# MicroPlayerSCH.net
KiCad netlist of a schematic drawn in Altium Designer
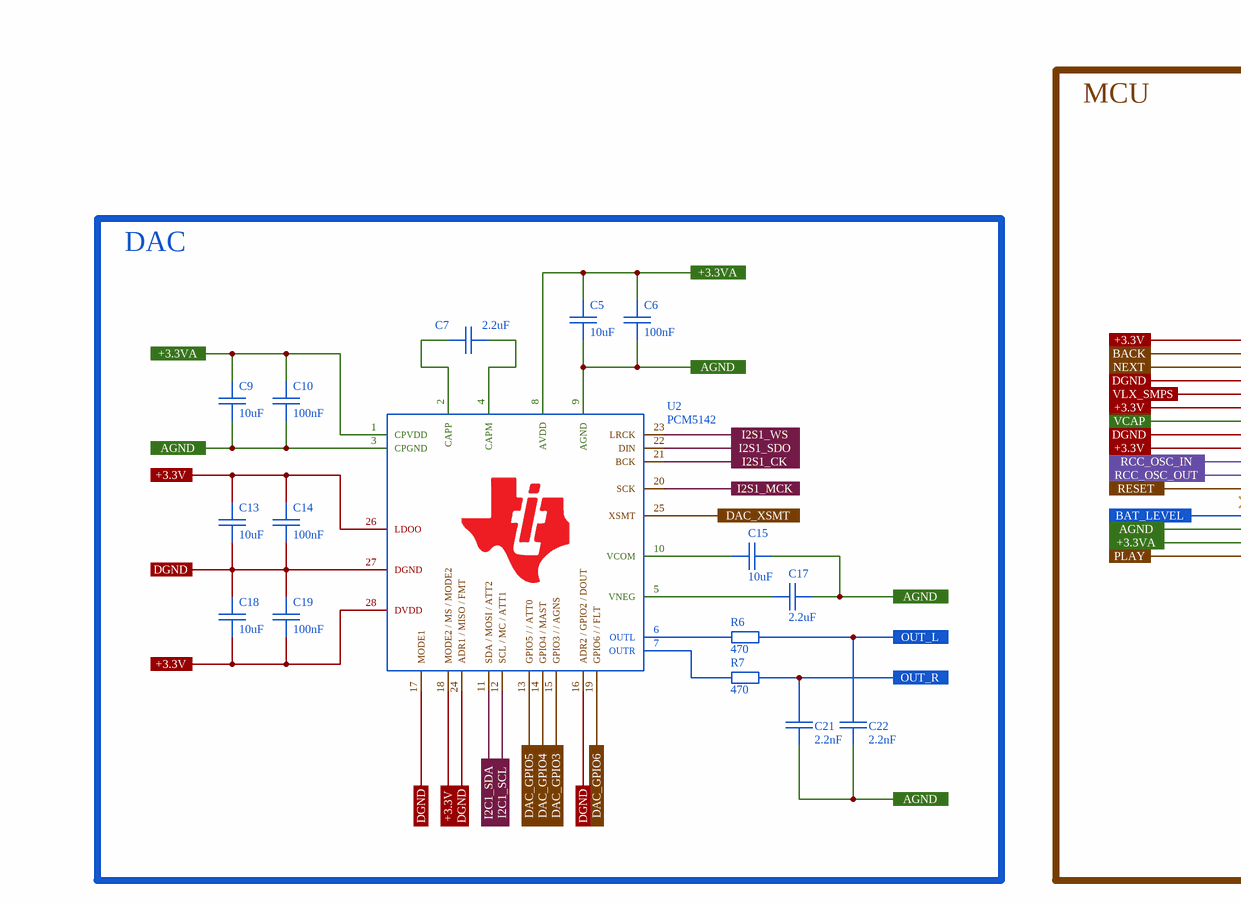
[diagram p0: MicroPlayerSCH.SchDoc, top left]
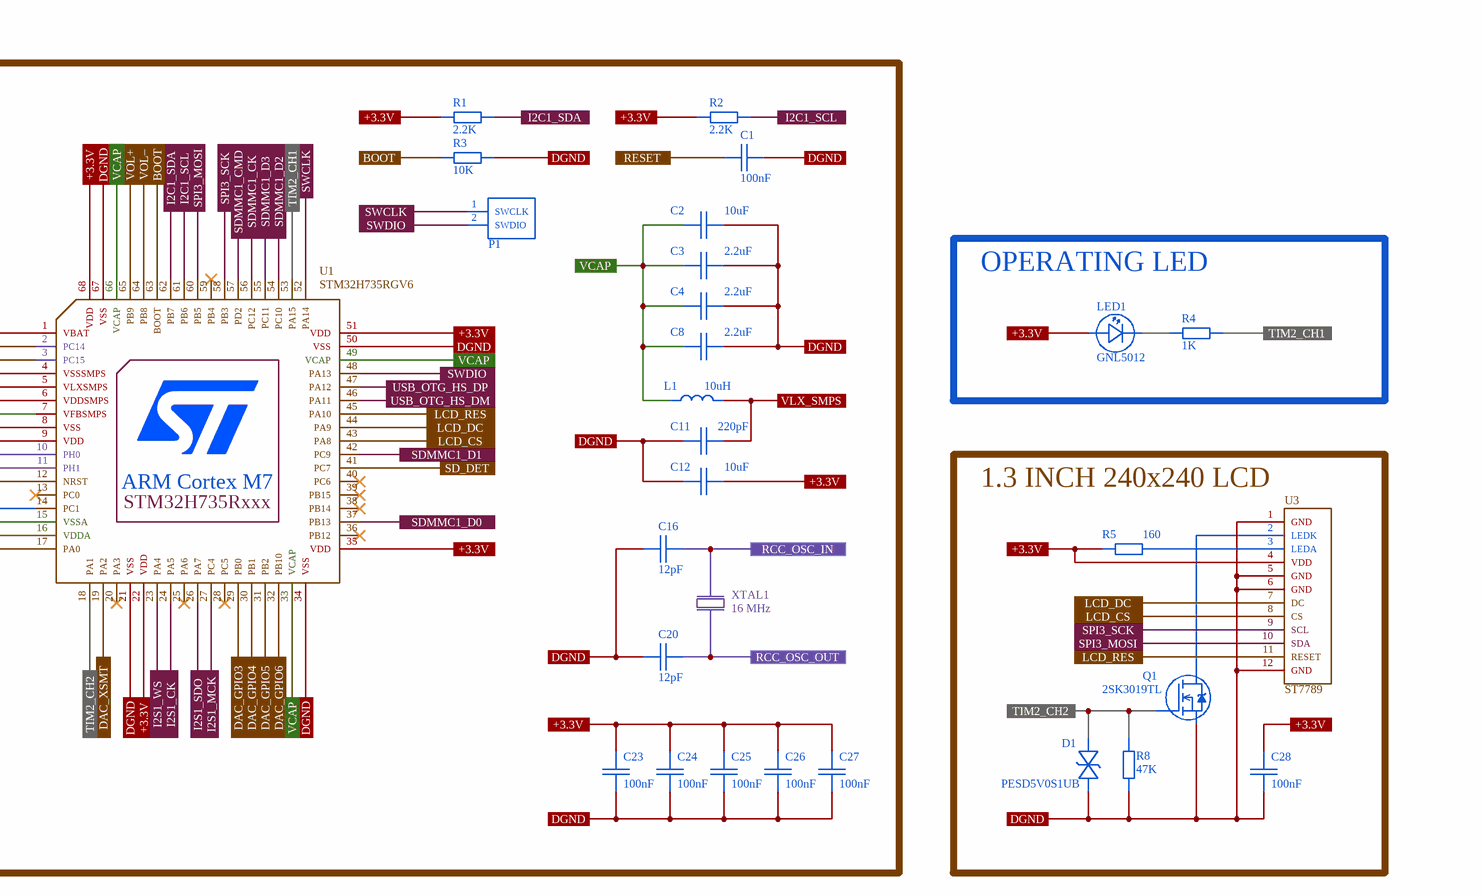
[diagram p1: MicroPlayerSCH.SchDoc, top right]
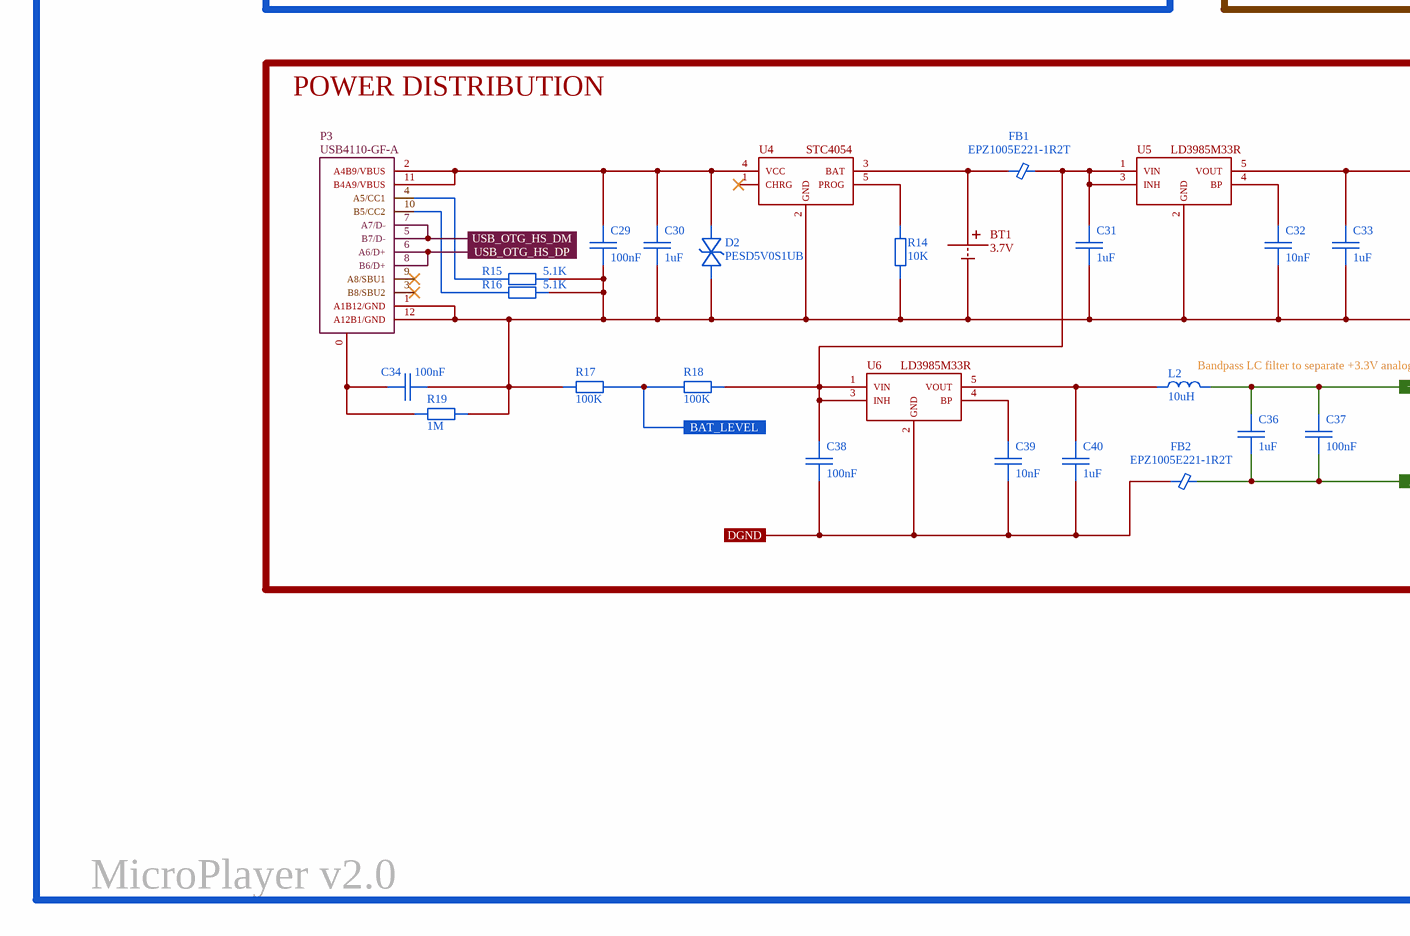
[diagram p2: MicroPlayerSCH.SchDoc, bottom left]
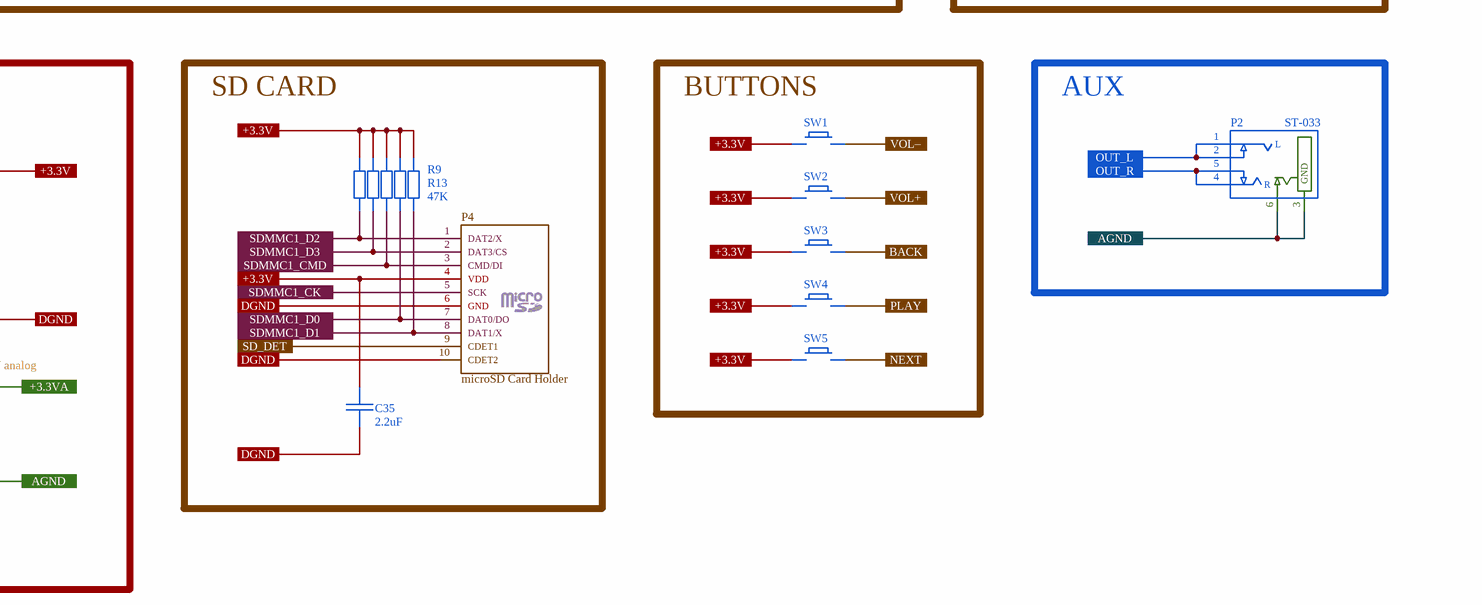
[diagram p3: MicroPlayerSCH.SchDoc, bottom right]

(export (version "E")
  (design (tool "Eeschema 10.0.6"))
  (components
    (comp (ref "BT1") (value "3.7V") (footprint "_2-PAD-SM") (libsource (lib "PowerUnits") (part "Battery")))
    (comp (ref "C1")
      (value "100nF")
      (footprint "C0402")
      (fields (field (name "VOLTAGE") "250V") (field (name "TOLERANCE") "5%"))
      (libsource (lib "CommonElements") (part "Cap"))
    )
    (comp (ref "C2")
      (value "10uF")
      (footprint "C0603")
      (fields (field (name "VOLTAGE") "250V") (field (name "TOLERANCE") "5%"))
      (libsource (lib "CommonElements") (part "Cap"))
    )
    (comp (ref "C3")
      (value "2.2uF")
      (footprint "C0402")
      (fields (field (name "VOLTAGE") "250V") (field (name "TOLERANCE") "5%"))
      (libsource (lib "CommonElements") (part "Cap"))
    )
    (comp (ref "C4")
      (value "2.2uF")
      (footprint "C0402")
      (fields (field (name "VOLTAGE") "250V") (field (name "TOLERANCE") "5%"))
      (libsource (lib "CommonElements") (part "Cap"))
    )
    (comp (ref "C5")
      (value "10uF")
      (footprint "C0603")
      (fields (field (name "VOLTAGE") "250V") (field (name "TOLERANCE") "5%"))
      (libsource (lib "CommonElements") (part "Cap"))
    )
    (comp (ref "C6")
      (value "100nF")
      (footprint "C0402")
      (fields (field (name "VOLTAGE") "250V") (field (name "TOLERANCE") "5%"))
      (libsource (lib "CommonElements") (part "Cap"))
    )
    (comp (ref "C7")
      (value "2.2uF")
      (footprint "C0402")
      (fields (field (name "VOLTAGE") "250V") (field (name "TOLERANCE") "5%"))
      (libsource (lib "CommonElements") (part "Cap"))
    )
    (comp (ref "C8")
      (value "2.2uF")
      (footprint "C0402")
      (fields (field (name "VOLTAGE") "250V") (field (name "TOLERANCE") "5%"))
      (libsource (lib "CommonElements") (part "Cap"))
    )
    (comp (ref "C9")
      (value "10uF")
      (footprint "C0603")
      (fields (field (name "VOLTAGE") "250V") (field (name "TOLERANCE") "5%"))
      (libsource (lib "CommonElements") (part "Cap"))
    )
    (comp (ref "C10")
      (value "100nF")
      (footprint "C0402")
      (fields (field (name "VOLTAGE") "250V") (field (name "TOLERANCE") "5%"))
      (libsource (lib "CommonElements") (part "Cap"))
    )
    (comp (ref "C11")
      (value "220pF")
      (footprint "C0402")
      (fields (field (name "VOLTAGE") "250V") (field (name "TOLERANCE") "5%"))
      (libsource (lib "CommonElements") (part "Cap"))
    )
    (comp (ref "C12")
      (value "10uF")
      (footprint "C0603")
      (fields (field (name "VOLTAGE") "250V") (field (name "TOLERANCE") "5%"))
      (libsource (lib "CommonElements") (part "Cap"))
    )
    (comp (ref "C13")
      (value "10uF")
      (footprint "C0603")
      (fields (field (name "VOLTAGE") "250V") (field (name "TOLERANCE") "5%"))
      (libsource (lib "CommonElements") (part "Cap"))
    )
    (comp (ref "C14")
      (value "100nF")
      (footprint "C0402")
      (fields (field (name "VOLTAGE") "250V") (field (name "TOLERANCE") "5%"))
      (libsource (lib "CommonElements") (part "Cap"))
    )
    (comp (ref "C15")
      (value "10uF")
      (footprint "C0603")
      (fields (field (name "VOLTAGE") "250V") (field (name "TOLERANCE") "5%"))
      (libsource (lib "CommonElements") (part "Cap"))
    )
    (comp (ref "C16")
      (value "12pF")
      (footprint "C0402")
      (fields (field (name "VOLTAGE") "250V") (field (name "TOLERANCE") "5%"))
      (libsource (lib "CommonElements") (part "Cap"))
    )
    (comp (ref "C17")
      (value "2.2uF")
      (footprint "C0402")
      (fields (field (name "VOLTAGE") "250V") (field (name "TOLERANCE") "5%"))
      (libsource (lib "CommonElements") (part "Cap"))
    )
    (comp (ref "C18")
      (value "10uF")
      (footprint "C0603")
      (fields (field (name "VOLTAGE") "250V") (field (name "TOLERANCE") "5%"))
      (libsource (lib "CommonElements") (part "Cap"))
    )
    (comp (ref "C19")
      (value "100nF")
      (footprint "C0402")
      (fields (field (name "VOLTAGE") "250V") (field (name "TOLERANCE") "5%"))
      (libsource (lib "CommonElements") (part "Cap"))
    )
    (comp (ref "C20")
      (value "12pF")
      (footprint "C0402")
      (fields (field (name "VOLTAGE") "250V") (field (name "TOLERANCE") "5%"))
      (libsource (lib "CommonElements") (part "Cap"))
    )
    (comp (ref "C21")
      (value "2.2nF")
      (footprint "C0402")
      (fields (field (name "VOLTAGE") "250V") (field (name "TOLERANCE") "5%"))
      (libsource (lib "CommonElements") (part "Cap"))
    )
    (comp (ref "C22")
      (value "2.2nF")
      (footprint "C0402")
      (fields (field (name "VOLTAGE") "250V") (field (name "TOLERANCE") "5%"))
      (libsource (lib "CommonElements") (part "Cap"))
    )
    (comp (ref "C23")
      (value "100nF")
      (footprint "C0402")
      (fields (field (name "VOLTAGE") "250V") (field (name "TOLERANCE") "5%"))
      (libsource (lib "CommonElements") (part "Cap"))
    )
    (comp (ref "C24")
      (value "100nF")
      (footprint "C0402")
      (fields (field (name "VOLTAGE") "250V") (field (name "TOLERANCE") "5%"))
      (libsource (lib "CommonElements") (part "Cap"))
    )
    (comp (ref "C25")
      (value "100nF")
      (footprint "C0402")
      (fields (field (name "VOLTAGE") "250V") (field (name "TOLERANCE") "5%"))
      (libsource (lib "CommonElements") (part "Cap"))
    )
    (comp (ref "C26")
      (value "100nF")
      (footprint "C0402")
      (fields (field (name "VOLTAGE") "250V") (field (name "TOLERANCE") "5%"))
      (libsource (lib "CommonElements") (part "Cap"))
    )
    (comp (ref "C27")
      (value "100nF")
      (footprint "C0402")
      (fields (field (name "VOLTAGE") "250V") (field (name "TOLERANCE") "5%"))
      (libsource (lib "CommonElements") (part "Cap"))
    )
    (comp (ref "C28")
      (value "100nF")
      (footprint "C0402")
      (fields (field (name "VOLTAGE") "250V") (field (name "TOLERANCE") "5%"))
      (libsource (lib "CommonElements") (part "Cap"))
    )
    (comp (ref "C29")
      (value "100nF")
      (footprint "C0402")
      (fields (field (name "VOLTAGE") "250V") (field (name "TOLERANCE") "5%"))
      (libsource (lib "CommonElements") (part "Cap"))
    )
    (comp (ref "C30")
      (value "1uF")
      (footprint "C0402")
      (fields (field (name "VOLTAGE") "250V") (field (name "TOLERANCE") "5%"))
      (libsource (lib "CommonElements") (part "Cap"))
    )
    (comp (ref "C31")
      (value "1uF")
      (footprint "C0402")
      (fields (field (name "VOLTAGE") "250V") (field (name "TOLERANCE") "5%"))
      (libsource (lib "CommonElements") (part "Cap"))
    )
    (comp (ref "C32")
      (value "10nF")
      (footprint "C0402")
      (fields (field (name "VOLTAGE") "250V") (field (name "TOLERANCE") "5%"))
      (libsource (lib "CommonElements") (part "Cap"))
    )
    (comp (ref "C33")
      (value "1uF")
      (footprint "C0402")
      (fields (field (name "VOLTAGE") "250V") (field (name "TOLERANCE") "5%"))
      (libsource (lib "CommonElements") (part "Cap"))
    )
    (comp (ref "C34")
      (value "100nF")
      (footprint "C0402")
      (fields (field (name "VOLTAGE") "250V") (field (name "TOLERANCE") "5%"))
      (libsource (lib "CommonElements") (part "Cap"))
    )
    (comp (ref "C35")
      (value "2.2uF")
      (footprint "C0402")
      (fields (field (name "VOLTAGE") "250V") (field (name "TOLERANCE") "5%"))
      (libsource (lib "CommonElements") (part "Cap"))
    )
    (comp (ref "C36")
      (value "1uF")
      (footprint "C0402")
      (fields (field (name "VOLTAGE") "250V") (field (name "TOLERANCE") "5%"))
      (libsource (lib "CommonElements") (part "Cap"))
    )
    (comp (ref "C37")
      (value "100nF")
      (footprint "C0402")
      (fields (field (name "VOLTAGE") "250V") (field (name "TOLERANCE") "5%"))
      (libsource (lib "CommonElements") (part "Cap"))
    )
    (comp (ref "C38")
      (value "100nF")
      (footprint "C0402")
      (fields (field (name "VOLTAGE") "250V") (field (name "TOLERANCE") "5%"))
      (libsource (lib "CommonElements") (part "Cap"))
    )
    (comp (ref "C39")
      (value "10nF")
      (footprint "C0402")
      (fields (field (name "VOLTAGE") "250V") (field (name "TOLERANCE") "5%"))
      (libsource (lib "CommonElements") (part "Cap"))
    )
    (comp (ref "C40")
      (value "1uF")
      (footprint "C0402")
      (fields (field (name "VOLTAGE") "250V") (field (name "TOLERANCE") "5%"))
      (libsource (lib "CommonElements") (part "Cap"))
    )
    (comp (ref "D1")
      (value "PESD5V0S1UB")
      (footprint "SOD-523")
      (libsource (lib "CommonElements") (part "Suppressor"))
    )
    (comp (ref "D2")
      (value "PESD5V0S1UB")
      (footprint "SOD-523")
      (libsource (lib "CommonElements") (part "Suppressor"))
    )
    (comp (ref "FB1")
      (value "EPZ1005E221-1R2T")
      (footprint "L0402")
      (libsource (lib "CommonElements") (part "Ferrite Bead"))
    )
    (comp (ref "FB2")
      (value "EPZ1005E221-1R2T")
      (footprint "L0402")
      (libsource (lib "CommonElements") (part "Ferrite Bead"))
    )
    (comp (ref "L1")
      (value "10uH")
      (footprint "L0603")
      (fields (field (name "TOLERANCE") "5%"))
      (libsource (lib "CommonElements") (part "Inductor"))
    )
    (comp (ref "L2")
      (value "10uH")
      (footprint "L0603")
      (fields (field (name "TOLERANCE") "30%") (field (name "PART NUMBER") "LQM21FN100N00K"))
      (libsource (lib "CommonElements") (part "Inductor"))
    )
    (comp (ref "LED1")
      (value "GNL5012")
      (footprint "LED0603")
      (libsource (lib "CommonElements") (part "LED"))
    )
    (comp (ref "P1") (value "P2") (footprint "_2-PAD-SM") (libsource (lib "Connectors") (part "P2")))
    (comp (ref "P2")
      (value "ST-033")
      (footprint "_3-PAD-TH")
      (libsource (lib "Connectors") (part "AJack Socket Stereo"))
    )
    (comp (ref "P3")
      (value "USB4110-GF-A")
      (footprint "USB-TYPE-C")
      (libsource (lib "Connectors") (part "USB Type C with 0"))
    )
    (comp (ref "P4")
      (value "microSD Card Holder")
      (footprint "SD-05")
      (libsource (lib "Connectors") (part "MicroSD-CD2"))
    )
    (comp (ref "Q1")
      (value "2SK3019TL")
      (footprint "SOT-416FL")
      (libsource (lib "CommonElements") (part "MOSFET-N"))
    )
    (comp (ref "R1")
      (value "2.2K")
      (footprint "R0402")
      (fields (field (name "TOLERANCE") "5%") (field (name "POWER") "0.125W"))
      (libsource (lib "CommonElements") (part "Res"))
    )
    (comp (ref "R2")
      (value "2.2K")
      (footprint "R0402")
      (fields (field (name "TOLERANCE") "5%") (field (name "POWER") "0.125W"))
      (libsource (lib "CommonElements") (part "Res"))
    )
    (comp (ref "R3")
      (value "10K")
      (footprint "R0402")
      (fields (field (name "TOLERANCE") "5%") (field (name "POWER") "0.125W"))
      (libsource (lib "CommonElements") (part "Res"))
    )
    (comp (ref "R4")
      (value "1K")
      (footprint "R0402")
      (fields (field (name "TOLERANCE") "5%") (field (name "POWER") "0.125W"))
      (libsource (lib "CommonElements") (part "Res"))
    )
    (comp (ref "R5")
      (value "160")
      (footprint "R0402")
      (fields (field (name "TOLERANCE") "5%") (field (name "POWER") "0.125W"))
      (libsource (lib "CommonElements") (part "Res"))
    )
    (comp (ref "R6")
      (value "470")
      (footprint "R0402")
      (fields (field (name "TOLERANCE") "5%") (field (name "POWER") "0.125W"))
      (libsource (lib "CommonElements") (part "Res"))
    )
    (comp (ref "R7")
      (value "470")
      (footprint "R0402")
      (fields (field (name "TOLERANCE") "5%") (field (name "POWER") "0.125W"))
      (libsource (lib "CommonElements") (part "Res"))
    )
    (comp (ref "R8")
      (value "47K")
      (footprint "R0402")
      (fields (field (name "TOLERANCE") "5%") (field (name "POWER") "0.125W"))
      (libsource (lib "CommonElements") (part "Res"))
    )
    (comp (ref "R9")
      (value "47K")
      (footprint "R0402")
      (fields (field (name "TOLERANCE") "5%") (field (name "POWER") "0.125W"))
      (libsource (lib "CommonElements") (part "Res"))
    )
    (comp (ref "R10")
      (value "47K")
      (footprint "R0402")
      (fields (field (name "TOLERANCE") "5%") (field (name "POWER") "0.125W"))
      (libsource (lib "CommonElements") (part "Res"))
    )
    (comp (ref "R11")
      (value "47K")
      (footprint "R0402")
      (fields (field (name "TOLERANCE") "5%") (field (name "POWER") "0.125W"))
      (libsource (lib "CommonElements") (part "Res"))
    )
    (comp (ref "R12")
      (value "47K")
      (footprint "R0402")
      (fields (field (name "TOLERANCE") "5%") (field (name "POWER") "0.125W"))
      (libsource (lib "CommonElements") (part "Res"))
    )
    (comp (ref "R13")
      (value "47K")
      (footprint "R0402")
      (fields (field (name "TOLERANCE") "5%") (field (name "POWER") "0.125W"))
      (libsource (lib "CommonElements") (part "Res"))
    )
    (comp (ref "R14")
      (value "10K")
      (footprint "R0402")
      (fields (field (name "TOLERANCE") "5%") (field (name "POWER") "0.125W"))
      (libsource (lib "CommonElements") (part "Res"))
    )
    (comp (ref "R15")
      (value "5.1K")
      (footprint "R0402")
      (fields (field (name "TOLERANCE") "5%") (field (name "POWER") "0.125W"))
      (libsource (lib "CommonElements") (part "Res"))
    )
    (comp (ref "R16")
      (value "5.1K")
      (footprint "R0402")
      (fields (field (name "TOLERANCE") "5%") (field (name "POWER") "0.125W"))
      (libsource (lib "CommonElements") (part "Res"))
    )
    (comp (ref "R17")
      (value "100K")
      (footprint "R0402")
      (fields (field (name "TOLERANCE") "5%") (field (name "POWER") "0.125W"))
      (libsource (lib "CommonElements") (part "Res"))
    )
    (comp (ref "R18")
      (value "100K")
      (footprint "R0402")
      (fields (field (name "TOLERANCE") "5%") (field (name "POWER") "0.125W"))
      (libsource (lib "CommonElements") (part "Res"))
    )
    (comp (ref "R19")
      (value "1M")
      (footprint "R0402")
      (fields (field (name "TOLERANCE") "5%") (field (name "POWER") "0.125W"))
      (libsource (lib "CommonElements") (part "Res"))
    )
    (comp (ref "SW1")
      (value "~")
      (footprint "BUT-SMD-4X3.5X2MM")
      (libsource (lib "CommonElements") (part "Button"))
    )
    (comp (ref "SW2")
      (value "~")
      (footprint "BUT-SMD-4X3.5X2MM")
      (libsource (lib "CommonElements") (part "Button"))
    )
    (comp (ref "SW3")
      (value "~")
      (footprint "BUT-SMD-4X3.5X2MM")
      (libsource (lib "CommonElements") (part "Button"))
    )
    (comp (ref "SW4")
      (value "~")
      (footprint "BUT-SMD-4X3.5X2MM")
      (libsource (lib "CommonElements") (part "Button"))
    )
    (comp (ref "SW5")
      (value "~")
      (footprint "BUT-SMD-4X3.5X2MM")
      (libsource (lib "CommonElements") (part "Button"))
    )
    (comp (ref "U1")
      (value "STM32H735RGV6")
      (footprint "VFQFPN68")
      (libsource (lib "STM32") (part "STM32H735Rxxx"))
    )
    (comp (ref "U2")
      (value "PCM5142")
      (footprint "TSSOP28")
      (description "2-VRMS DirectPath™, 112/106-dB Audio Stereo DAC With 32-bit, 384-kHz PCM Interface")
      (libsource (lib "Miscellaneous") (part "PCM514x"))
    )
    (comp (ref "U3")
      (value "ST7789")
      (footprint "1.3INCH_LCD_WELDED")
      (description "135x240 Display")
      (libsource (lib "Modules") (part "1.3inch TFT LCD 12-pin"))
    )
    (comp (ref "U4")
      (value "STC4054")
      (footprint "SOT-23-5")
      (description "800mA Standalone linear Li-Ion Battery charger with thermal regulation")
      (libsource (lib "PowerUnits") (part "STC4054"))
    )
    (comp (ref "U5")
      (value "LD3985M33R")
      (footprint "SOT-23-5")
      (description "Ultra low drop and low noise BiCMOS voltage regulators, 150 mA")
      (libsource (lib "PowerUnits") (part "LD3985"))
    )
    (comp (ref "U6")
      (value "LD3985M33R")
      (footprint "SOT-23-5")
      (description "Ultra low drop and low noise BiCMOS voltage regulators, 150 mA")
      (libsource (lib "PowerUnits") (part "LD3985"))
    )
    (comp (ref "XTAL1")
      (value "16 MHz")
      (footprint "7U")
      (fields (field (name "TOLERANCE") "0.001%"))
      (libsource (lib "CommonElements") (part "Crystal"))
    )
  )
  (nets
    (net (code "1") (name "/+3.3V") (class "Default")
      (node (ref "C12") (pin "1") (pintype "passive"))
      (node (ref "C13") (pin "1") (pintype "passive"))
      (node (ref "C14") (pin "1") (pintype "passive"))
      (node (ref "C18") (pin "2") (pintype "passive"))
      (node (ref "C19") (pin "2") (pintype "passive"))
      (node (ref "C23") (pin "2") (pintype "passive"))
      (node (ref "C24") (pin "2") (pintype "passive"))
      (node (ref "C25") (pin "2") (pintype "passive"))
      (node (ref "C26") (pin "2") (pintype "passive"))
      (node (ref "C27") (pin "2") (pintype "passive"))
      (node (ref "C28") (pin "2") (pintype "passive"))
      (node (ref "C33") (pin "2") (pintype "passive"))
      (node (ref "C35") (pin "1") (pintype "passive"))
      (node (ref "LED1") (pin "1") (pinfunction "Anode_1") (pintype "passive"))
      (node (ref "P4") (pin "4") (pinfunction "VDD_4") (pintype "passive"))
      (node (ref "R1") (pin "1") (pintype "passive"))
      (node (ref "R10") (pin "2") (pintype "passive"))
      (node (ref "R11") (pin "2") (pintype "passive"))
      (node (ref "R12") (pin "2") (pintype "passive"))
      (node (ref "R13") (pin "2") (pintype "passive"))
      (node (ref "R2") (pin "1") (pintype "passive"))
      (node (ref "R5") (pin "1") (pintype "passive"))
      (node (ref "R9") (pin "2") (pintype "passive"))
      (node (ref "SW1") (pin "1") (pintype "passive"))
      (node (ref "SW2") (pin "1") (pintype "passive"))
      (node (ref "SW3") (pin "1") (pintype "passive"))
      (node (ref "SW4") (pin "1") (pintype "passive"))
      (node (ref "SW5") (pin "1") (pintype "passive"))
      (node (ref "U1") (pin "1") (pinfunction "VBAT_1") (pintype "passive"))
      (node (ref "U1") (pin "22") (pinfunction "VDD_22") (pintype "passive"))
      (node (ref "U1") (pin "35") (pinfunction "VDD_35") (pintype "passive"))
      (node (ref "U1") (pin "51") (pinfunction "VDD_51") (pintype "passive"))
      (node (ref "U1") (pin "6") (pinfunction "VDDSMPS_6") (pintype "passive"))
      (node (ref "U1") (pin "68") (pinfunction "VDD_68") (pintype "passive"))
      (node (ref "U1") (pin "9") (pinfunction "VDD_9") (pintype "passive"))
      (node (ref "U2") (pin "18") (pinfunction "MODE2_/_MS_/_MODE2_18") (pintype "passive"))
      (node (ref "U2") (pin "26") (pinfunction "LDOO_26") (pintype "passive"))
      (node (ref "U2") (pin "28") (pinfunction "DVDD_28") (pintype "passive"))
      (node (ref "U3") (pin "4") (pinfunction "VDD_4") (pintype "passive"))
      (node (ref "U5") (pin "5") (pinfunction "VOUT_5") (pintype "passive"))
    )
    (net (code "2") (name "/+3.3VA") (class "Default")
      (node (ref "C10") (pin "1") (pintype "passive"))
      (node (ref "C36") (pin "1") (pintype "passive"))
      (node (ref "C37") (pin "1") (pintype "passive"))
      (node (ref "C5") (pin "1") (pintype "passive"))
      (node (ref "C6") (pin "1") (pintype "passive"))
      (node (ref "C9") (pin "1") (pintype "passive"))
      (node (ref "L2") (pin "2") (pintype "passive"))
      (node (ref "U1") (pin "16") (pinfunction "VDDA_16") (pintype "passive"))
      (node (ref "U2") (pin "1") (pinfunction "CPVDD_1") (pintype "passive"))
      (node (ref "U2") (pin "8") (pinfunction "AVDD_8") (pintype "passive"))
    )
    (net (code "3") (name "/AGND") (class "Default")
      (node (ref "C10") (pin "2") (pintype "passive"))
      (node (ref "C15") (pin "2") (pintype "passive"))
      (node (ref "C17") (pin "2") (pintype "passive"))
      (node (ref "C21") (pin "1") (pintype "passive"))
      (node (ref "C22") (pin "1") (pintype "passive"))
      (node (ref "C36") (pin "2") (pintype "passive"))
      (node (ref "C37") (pin "2") (pintype "passive"))
      (node (ref "C5") (pin "2") (pintype "passive"))
      (node (ref "C6") (pin "2") (pintype "passive"))
      (node (ref "C9") (pin "2") (pintype "passive"))
      (node (ref "FB2") (pin "2") (pintype "passive"))
      (node (ref "P2") (pin "3") (pinfunction "GND_3") (pintype "passive"))
      (node (ref "P2") (pin "6") (pintype "passive"))
      (node (ref "U1") (pin "15") (pinfunction "VSSA_15") (pintype "passive"))
      (node (ref "U2") (pin "3") (pinfunction "CPGND_3") (pintype "passive"))
      (node (ref "U2") (pin "9") (pinfunction "AGND_9") (pintype "passive"))
    )
    (net (code "4") (name "/BACK") (class "Default")
      (node (ref "SW3") (pin "2") (pintype "passive"))
      (node (ref "U1") (pin "2") (pinfunction "PC14_2") (pintype "passive"))
    )
    (net (code "5") (name "/BAT_LEVEL") (class "Default")
      (node (ref "R17") (pin "1") (pintype "passive"))
      (node (ref "R18") (pin "2") (pintype "passive"))
      (node (ref "U1") (pin "14") (pinfunction "PC1_14") (pintype "passive"))
    )
    (net (code "6") (name "/BOOT") (class "Default")
      (node (ref "R3") (pin "1") (pintype "passive"))
      (node (ref "U1") (pin "63") (pinfunction "BOOT_63") (pintype "passive"))
    )
    (net (code "7") (name "/DAC_GPIO3") (class "Default")
      (node (ref "U1") (pin "29") (pinfunction "PB0_29") (pintype "passive"))
      (node (ref "U2") (pin "15") (pinfunction "GPIO3_/_/_AGNS_15") (pintype "passive"))
    )
    (net (code "8") (name "/DAC_GPIO4") (class "Default")
      (node (ref "U1") (pin "30") (pinfunction "PB1_30") (pintype "passive"))
      (node (ref "U2") (pin "14") (pinfunction "GPIO4_/_MAST_14") (pintype "passive"))
    )
    (net (code "9") (name "/DAC_GPIO5") (class "Default")
      (node (ref "U1") (pin "31") (pinfunction "PB2_31") (pintype "passive"))
      (node (ref "U2") (pin "13") (pinfunction "GPIO5_/_/_ATT0_13") (pintype "passive"))
    )
    (net (code "10") (name "/DAC_GPIO6") (class "Default")
      (node (ref "U1") (pin "32") (pinfunction "PB10_32") (pintype "passive"))
      (node (ref "U2") (pin "19") (pinfunction "GPIO6_/_/_FLT_19") (pintype "passive"))
    )
    (net (code "11") (name "/DAC_XSMT") (class "Default")
      (node (ref "U1") (pin "19") (pinfunction "PA2_19") (pintype "passive"))
      (node (ref "U2") (pin "25") (pinfunction "XSMT_25") (pintype "passive"))
    )
    (net (code "12") (name "/DGND") (class "Default")
      (node (ref "BT1") (pin "2") (pintype "passive"))
      (node (ref "C1") (pin "1") (pintype "passive"))
      (node (ref "C11") (pin "2") (pintype "passive"))
      (node (ref "C12") (pin "2") (pintype "passive"))
      (node (ref "C13") (pin "2") (pintype "passive"))
      (node (ref "C14") (pin "2") (pintype "passive"))
      (node (ref "C16") (pin "2") (pintype "passive"))
      (node (ref "C18") (pin "1") (pintype "passive"))
      (node (ref "C19") (pin "1") (pintype "passive"))
      (node (ref "C2") (pin "1") (pintype "passive"))
      (node (ref "C20") (pin "2") (pintype "passive"))
      (node (ref "C23") (pin "1") (pintype "passive"))
      (node (ref "C24") (pin "1") (pintype "passive"))
      (node (ref "C25") (pin "1") (pintype "passive"))
      (node (ref "C26") (pin "1") (pintype "passive"))
      (node (ref "C27") (pin "1") (pintype "passive"))
      (node (ref "C28") (pin "1") (pintype "passive"))
      (node (ref "C29") (pin "1") (pintype "passive"))
      (node (ref "C3") (pin "1") (pintype "passive"))
      (node (ref "C30") (pin "2") (pintype "passive"))
      (node (ref "C31") (pin "1") (pintype "passive"))
      (node (ref "C32") (pin "1") (pintype "passive"))
      (node (ref "C33") (pin "1") (pintype "passive"))
      (node (ref "C34") (pin "1") (pintype "passive"))
      (node (ref "C35") (pin "2") (pintype "passive"))
      (node (ref "C38") (pin "1") (pintype "passive"))
      (node (ref "C39") (pin "1") (pintype "passive"))
      (node (ref "C4") (pin "1") (pintype "passive"))
      (node (ref "C40") (pin "1") (pintype "passive"))
      (node (ref "C8") (pin "1") (pintype "passive"))
      (node (ref "D1") (pin "1") (pintype "passive"))
      (node (ref "D2") (pin "1") (pintype "passive"))
      (node (ref "FB2") (pin "1") (pintype "passive"))
      (node (ref "P3") (pin "1") (pinfunction "A1B12/GND_1") (pintype "passive"))
      (node (ref "P3") (pin "12") (pinfunction "A12B1/GND_12") (pintype "passive"))
      (node (ref "P4") (pin "10") (pinfunction "CDET2_10") (pintype "passive"))
      (node (ref "P4") (pin "6") (pinfunction "GND_6") (pintype "passive"))
      (node (ref "Q1") (pin "2") (pinfunction "S_2") (pintype "passive"))
      (node (ref "R14") (pin "1") (pintype "passive"))
      (node (ref "R15") (pin "1") (pintype "passive"))
      (node (ref "R16") (pin "1") (pintype "passive"))
      (node (ref "R17") (pin "2") (pintype "passive"))
      (node (ref "R19") (pin "1") (pintype "passive"))
      (node (ref "R3") (pin "2") (pintype "passive"))
      (node (ref "R8") (pin "1") (pintype "passive"))
      (node (ref "U1") (pin "21") (pinfunction "VSS_21") (pintype "passive"))
      (node (ref "U1") (pin "34") (pinfunction "VSS_34") (pintype "passive"))
      (node (ref "U1") (pin "4") (pinfunction "VSSSMPS_4") (pintype "passive"))
      (node (ref "U1") (pin "50") (pinfunction "VSS_50") (pintype "passive"))
      (node (ref "U1") (pin "67") (pinfunction "VSS_67") (pintype "passive"))
      (node (ref "U1") (pin "8") (pinfunction "VSS_8") (pintype "passive"))
      (node (ref "U2") (pin "16") (pinfunction "ADR2_/_GPIO2_/_DOUT_16") (pintype "passive"))
      (node (ref "U2") (pin "17") (pinfunction "MODE1_17") (pintype "passive"))
      (node (ref "U2") (pin "24") (pinfunction "ADR1_/_MISO_/_FMT_24") (pintype "passive"))
      (node (ref "U2") (pin "27") (pinfunction "DGND_27") (pintype "passive"))
      (node (ref "U3") (pin "1") (pinfunction "GND_1") (pintype "passive"))
      (node (ref "U3") (pin "12") (pinfunction "GND_12") (pintype "passive"))
      (node (ref "U3") (pin "5") (pinfunction "GND_5") (pintype "passive"))
      (node (ref "U3") (pin "6") (pinfunction "GND_6") (pintype "passive"))
      (node (ref "U4") (pin "2") (pinfunction "GND_2") (pintype "passive"))
      (node (ref "U5") (pin "2") (pinfunction "GND_2") (pintype "passive"))
      (node (ref "U6") (pin "2") (pinfunction "GND_2") (pintype "passive"))
    )
    (net (code "13") (name "/I2C1_SCL") (class "Default")
      (node (ref "R2") (pin "2") (pintype "passive"))
      (node (ref "U1") (pin "61") (pinfunction "PB6_61") (pintype "passive"))
      (node (ref "U2") (pin "12") (pinfunction "SCL_/_MC_/_ATT1_12") (pintype "passive"))
    )
    (net (code "14") (name "/I2C1_SDA") (class "Default")
      (node (ref "R1") (pin "2") (pintype "passive"))
      (node (ref "U1") (pin "62") (pinfunction "PB7_62") (pintype "passive"))
      (node (ref "U2") (pin "11") (pinfunction "SDA_/_MOSI_/_ATT2_11") (pintype "passive"))
    )
    (net (code "15") (name "/I2S1_CK") (class "Default")
      (node (ref "U1") (pin "24") (pinfunction "PA5_24") (pintype "passive"))
      (node (ref "U2") (pin "21") (pinfunction "BCK_21") (pintype "passive"))
    )
    (net (code "16") (name "/I2S1_MCK") (class "Default")
      (node (ref "U1") (pin "27") (pinfunction "PC4_27") (pintype "passive"))
      (node (ref "U2") (pin "20") (pinfunction "SCK_20") (pintype "passive"))
    )
    (net (code "17") (name "/I2S1_SDO") (class "Default")
      (node (ref "U1") (pin "26") (pinfunction "PA7_26") (pintype "passive"))
      (node (ref "U2") (pin "22") (pinfunction "DIN_22") (pintype "passive"))
    )
    (net (code "18") (name "/I2S1_WS") (class "Default")
      (node (ref "U1") (pin "23") (pinfunction "PA4_23") (pintype "passive"))
      (node (ref "U2") (pin "23") (pinfunction "LRCK_23") (pintype "passive"))
    )
    (net (code "19") (name "/LCD_CS") (class "Default")
      (node (ref "U1") (pin "43") (pinfunction "PA8_43") (pintype "passive"))
      (node (ref "U3") (pin "8") (pinfunction "CS_8") (pintype "passive"))
    )
    (net (code "20") (name "/LCD_DC") (class "Default")
      (node (ref "U1") (pin "44") (pinfunction "PA9_44") (pintype "passive"))
      (node (ref "U3") (pin "7") (pinfunction "DC_7") (pintype "passive"))
    )
    (net (code "21") (name "/LCD_RES") (class "Default")
      (node (ref "U1") (pin "45") (pinfunction "PA10_45") (pintype "passive"))
      (node (ref "U3") (pin "11") (pinfunction "RESET_11") (pintype "passive"))
    )
    (net (code "22") (name "/NEXT") (class "Default")
      (node (ref "SW5") (pin "2") (pintype "passive"))
      (node (ref "U1") (pin "3") (pinfunction "PC15_3") (pintype "passive"))
    )
    (net (code "23") (name "/OUT_L") (class "Default")
      (node (ref "C22") (pin "2") (pintype "passive"))
      (node (ref "P2") (pin "1") (pinfunction "L_1") (pintype "passive"))
      (node (ref "P2") (pin "2") (pintype "passive"))
      (node (ref "R6") (pin "1") (pintype "passive"))
    )
    (net (code "24") (name "/OUT_R") (class "Default")
      (node (ref "C21") (pin "2") (pintype "passive"))
      (node (ref "P2") (pin "4") (pinfunction "R_4") (pintype "passive"))
      (node (ref "P2") (pin "5") (pintype "passive"))
      (node (ref "R7") (pin "1") (pintype "passive"))
    )
    (net (code "25") (name "/PLAY") (class "Default")
      (node (ref "SW4") (pin "2") (pintype "passive"))
      (node (ref "U1") (pin "17") (pinfunction "PA0_17") (pintype "passive"))
    )
    (net (code "26") (name "/RCC_OSC_IN") (class "Default")
      (node (ref "C16") (pin "1") (pintype "passive"))
      (node (ref "U1") (pin "10") (pinfunction "PH0_10") (pintype "passive"))
      (node (ref "XTAL1") (pin "1") (pintype "passive"))
    )
    (net (code "27") (name "/RCC_OSC_OUT") (class "Default")
      (node (ref "C20") (pin "1") (pintype "passive"))
      (node (ref "U1") (pin "11") (pinfunction "PH1_11") (pintype "passive"))
      (node (ref "XTAL1") (pin "2") (pintype "passive"))
    )
    (net (code "28") (name "/RESET") (class "Default")
      (node (ref "C1") (pin "2") (pintype "passive"))
      (node (ref "U1") (pin "12") (pinfunction "NRST_12") (pintype "passive"))
    )
    (net (code "29") (name "/SDMMC1_CK") (class "Default")
      (node (ref "P4") (pin "5") (pinfunction "SCK_5") (pintype "passive"))
      (node (ref "U1") (pin "56") (pinfunction "PC12_56") (pintype "passive"))
    )
    (net (code "30") (name "/SDMMC1_CMD") (class "Default")
      (node (ref "P4") (pin "3") (pinfunction "CMD/DI_3") (pintype "passive"))
      (node (ref "R11") (pin "1") (pintype "passive"))
      (node (ref "U1") (pin "57") (pinfunction "PD2_57") (pintype "passive"))
    )
    (net (code "31") (name "/SDMMC1_D0") (class "Default")
      (node (ref "P4") (pin "7") (pinfunction "DAT0/DO_7") (pintype "passive"))
      (node (ref "R12") (pin "1") (pintype "passive"))
      (node (ref "U1") (pin "37") (pinfunction "PB13_37") (pintype "passive"))
    )
    (net (code "32") (name "/SDMMC1_D1") (class "Default")
      (node (ref "P4") (pin "8") (pinfunction "DAT1/X_8") (pintype "passive"))
      (node (ref "R13") (pin "1") (pintype "passive"))
      (node (ref "U1") (pin "42") (pinfunction "PC9_42") (pintype "passive"))
    )
    (net (code "33") (name "/SDMMC1_D2") (class "Default")
      (node (ref "P4") (pin "1") (pinfunction "DAT2/X_1") (pintype "passive"))
      (node (ref "R9") (pin "1") (pintype "passive"))
      (node (ref "U1") (pin "54") (pinfunction "PC10_54") (pintype "passive"))
    )
    (net (code "34") (name "/SDMMC1_D3") (class "Default")
      (node (ref "P4") (pin "2") (pinfunction "DAT3/CS_2") (pintype "passive"))
      (node (ref "R10") (pin "1") (pintype "passive"))
      (node (ref "U1") (pin "55") (pinfunction "PC11_55") (pintype "passive"))
    )
    (net (code "35") (name "/SD_DET") (class "Default")
      (node (ref "P4") (pin "9") (pinfunction "CDET1_9") (pintype "passive"))
      (node (ref "U1") (pin "41") (pinfunction "PC7_41") (pintype "passive"))
    )
    (net (code "36") (name "/SPI3_MOSI") (class "Default")
      (node (ref "U1") (pin "60") (pinfunction "PB5_60") (pintype "passive"))
      (node (ref "U3") (pin "10") (pinfunction "SDA_10") (pintype "passive"))
    )
    (net (code "37") (name "/SPI3_SCK") (class "Default")
      (node (ref "U1") (pin "58") (pinfunction "PB3_58") (pintype "passive"))
      (node (ref "U3") (pin "9") (pinfunction "SCL_9") (pintype "passive"))
    )
    (net (code "38") (name "/SWCLK") (class "Default")
      (node (ref "P1") (pin "1") (pinfunction "SWCLK_1") (pintype "passive"))
      (node (ref "U1") (pin "52") (pinfunction "PA14_52") (pintype "passive"))
    )
    (net (code "39") (name "/SWDIO") (class "Default")
      (node (ref "P1") (pin "2") (pinfunction "SWDIO_2") (pintype "passive"))
      (node (ref "U1") (pin "48") (pinfunction "PA13_48") (pintype "passive"))
    )
    (net (code "40") (name "/TIM2_CH1") (class "Default")
      (node (ref "R4") (pin "1") (pintype "passive"))
      (node (ref "U1") (pin "53") (pinfunction "PA15_53") (pintype "passive"))
    )
    (net (code "41") (name "/TIM2_CH2") (class "Default")
      (node (ref "D1") (pin "2") (pintype "passive"))
      (node (ref "Q1") (pin "1") (pinfunction "G_1") (pintype "passive"))
      (node (ref "R8") (pin "2") (pintype "passive"))
      (node (ref "U1") (pin "18") (pinfunction "PA1_18") (pintype "passive"))
    )
    (net (code "42") (name "/USB_OTG_HS_DM") (class "Default")
      (node (ref "P3") (pin "5") (pinfunction "B7/D-_5") (pintype "passive"))
      (node (ref "P3") (pin "7") (pinfunction "A7/D-_7") (pintype "passive"))
      (node (ref "U1") (pin "46") (pinfunction "PA11_46") (pintype "passive"))
    )
    (net (code "43") (name "/USB_OTG_HS_DP") (class "Default")
      (node (ref "P3") (pin "6") (pinfunction "A6/D+_6") (pintype "passive"))
      (node (ref "P3") (pin "8") (pinfunction "B6/D+_8") (pintype "passive"))
      (node (ref "U1") (pin "47") (pinfunction "PA12_47") (pintype "passive"))
    )
    (net (code "44") (name "/VCAP") (class "Default")
      (node (ref "C2") (pin "2") (pintype "passive"))
      (node (ref "C3") (pin "2") (pintype "passive"))
      (node (ref "C4") (pin "2") (pintype "passive"))
      (node (ref "C8") (pin "2") (pintype "passive"))
      (node (ref "L1") (pin "1") (pintype "passive"))
      (node (ref "U1") (pin "33") (pinfunction "VCAP_33") (pintype "passive"))
      (node (ref "U1") (pin "49") (pinfunction "VCAP_49") (pintype "passive"))
      (node (ref "U1") (pin "66") (pinfunction "VCAP_66") (pintype "passive"))
      (node (ref "U1") (pin "7") (pinfunction "VFBSMPS_7") (pintype "passive"))
    )
    (net (code "45") (name "/VLX_SMPS") (class "Default")
      (node (ref "C11") (pin "1") (pintype "passive"))
      (node (ref "L1") (pin "2") (pintype "passive"))
      (node (ref "U1") (pin "5") (pinfunction "VLXSMPS_5") (pintype "passive"))
    )
    (net (code "46") (name "/VOL+") (class "Default")
      (node (ref "SW2") (pin "2") (pintype "passive"))
      (node (ref "U1") (pin "65") (pinfunction "PB9_65") (pintype "passive"))
    )
    (net (code "47") (name "/VOL–") (class "Default")
      (node (ref "SW1") (pin "2") (pintype "passive"))
      (node (ref "U1") (pin "64") (pinfunction "PB8_64") (pintype "passive"))
    )
    (net (code "48") (name "Net-(C34-Pad2)") (class "Default")
      (node (ref "C34") (pin "2") (pintype "passive"))
      (node (ref "P3") (pin "0") (pintype "passive"))
      (node (ref "R19") (pin "2") (pintype "passive"))
    )
    (net (code "49") (name "Net-(LED1-Cathode)") (class "Default")
      (node (ref "LED1") (pin "2") (pinfunction "Cathode_2") (pintype "passive"))
      (node (ref "R4") (pin "2") (pintype "passive"))
    )
    (net (code "50") (name "Net-(P3-A4B9{slash}VBUS)") (class "Default")
      (node (ref "C29") (pin "2") (pintype "passive"))
      (node (ref "C30") (pin "1") (pintype "passive"))
      (node (ref "D2") (pin "2") (pintype "passive"))
      (node (ref "P3") (pin "11") (pinfunction "B4A9/VBUS_11") (pintype "passive"))
      (node (ref "P3") (pin "2") (pinfunction "A4B9/VBUS_2") (pintype "passive"))
      (node (ref "U4") (pin "4") (pinfunction "VCC_4") (pintype "passive"))
    )
    (net (code "51") (name "Net-(P3-A5{slash}CC1)") (class "Default")
      (node (ref "P3") (pin "4") (pinfunction "A5/CC1_4") (pintype "passive"))
      (node (ref "R15") (pin "2") (pintype "passive"))
    )
    (net (code "52") (name "Net-(P3-B5{slash}CC2)") (class "Default")
      (node (ref "P3") (pin "10") (pinfunction "B5/CC2_10") (pintype "passive"))
      (node (ref "R16") (pin "2") (pintype "passive"))
    )
    (net (code "53") (name "Net-(Q1-D)") (class "Default")
      (node (ref "Q1") (pin "3") (pinfunction "D_3") (pintype "passive"))
      (node (ref "U3") (pin "2") (pinfunction "LEDK_2") (pintype "passive"))
    )
    (net (code "54") (name "Net-(U2-CAPM)") (class "Default")
      (node (ref "C7") (pin "2") (pintype "passive"))
      (node (ref "U2") (pin "4") (pinfunction "CAPM_4") (pintype "passive"))
    )
    (net (code "55") (name "Net-(U2-CAPP)") (class "Default")
      (node (ref "C7") (pin "1") (pintype "passive"))
      (node (ref "U2") (pin "2") (pinfunction "CAPP_2") (pintype "passive"))
    )
    (net (code "56") (name "Net-(U2-OUTL)") (class "Default")
      (node (ref "R6") (pin "2") (pintype "passive"))
      (node (ref "U2") (pin "6") (pinfunction "OUTL_6") (pintype "passive"))
    )
    (net (code "57") (name "Net-(U2-OUTR)") (class "Default")
      (node (ref "R7") (pin "2") (pintype "passive"))
      (node (ref "U2") (pin "7") (pinfunction "OUTR_7") (pintype "passive"))
    )
    (net (code "58") (name "Net-(U2-VCOM)") (class "Default")
      (node (ref "C15") (pin "1") (pintype "passive"))
      (node (ref "U2") (pin "10") (pinfunction "VCOM_10") (pintype "passive"))
    )
    (net (code "59") (name "Net-(U2-VNEG)") (class "Default")
      (node (ref "C17") (pin "1") (pintype "passive"))
      (node (ref "U2") (pin "5") (pinfunction "VNEG_5") (pintype "passive"))
    )
    (net (code "60") (name "Net-(U3-LEDA)") (class "Default")
      (node (ref "R5") (pin "2") (pintype "passive"))
      (node (ref "U3") (pin "3") (pinfunction "LEDA_3") (pintype "passive"))
    )
    (net (code "61") (name "Net-(U4-BAT)") (class "Default")
      (node (ref "BT1") (pin "1") (pintype "passive"))
      (node (ref "FB1") (pin "1") (pintype "passive"))
      (node (ref "U4") (pin "3") (pinfunction "BAT_3") (pintype "passive"))
    )
    (net (code "62") (name "Net-(U4-PROG)") (class "Default")
      (node (ref "R14") (pin "2") (pintype "passive"))
      (node (ref "U4") (pin "5") (pinfunction "PROG_5") (pintype "passive"))
    )
    (net (code "63") (name "Net-(U5-BP)") (class "Default")
      (node (ref "C32") (pin "2") (pintype "passive"))
      (node (ref "U5") (pin "4") (pinfunction "BP_4") (pintype "passive"))
    )
    (net (code "64") (name "Net-(U5-INH)") (class "Default")
      (node (ref "C31") (pin "2") (pintype "passive"))
      (node (ref "C38") (pin "2") (pintype "passive"))
      (node (ref "FB1") (pin "2") (pintype "passive"))
      (node (ref "R18") (pin "1") (pintype "passive"))
      (node (ref "U5") (pin "1") (pinfunction "VIN_1") (pintype "passive"))
      (node (ref "U5") (pin "3") (pinfunction "INH_3") (pintype "passive"))
      (node (ref "U6") (pin "1") (pinfunction "VIN_1") (pintype "passive"))
      (node (ref "U6") (pin "3") (pinfunction "INH_3") (pintype "passive"))
    )
    (net (code "65") (name "Net-(U6-BP)") (class "Default")
      (node (ref "C39") (pin "2") (pintype "passive"))
      (node (ref "U6") (pin "4") (pinfunction "BP_4") (pintype "passive"))
    )
    (net (code "66") (name "Net-(U6-VOUT)") (class "Default")
      (node (ref "C40") (pin "2") (pintype "passive"))
      (node (ref "L2") (pin "1") (pintype "passive"))
      (node (ref "U6") (pin "5") (pinfunction "VOUT_5") (pintype "passive"))
    )
    (net (code "67") (name "unconnected-(P3-A8{slash}SBU1-Pad9)") (class "Default")
      (node (ref "P3") (pin "9") (pinfunction "A8/SBU1_9") (pintype "passive+no_connect"))
    )
    (net (code "68") (name "unconnected-(P3-B8{slash}SBU2-Pad3)") (class "Default")
      (node (ref "P3") (pin "3") (pinfunction "B8/SBU2_3") (pintype "passive+no_connect"))
    )
    (net (code "69") (name "unconnected-(U1-PA3-Pad20)") (class "Default")
      (node (ref "U1") (pin "20") (pinfunction "PA3_20") (pintype "passive+no_connect"))
    )
    (net (code "70") (name "unconnected-(U1-PA6-Pad25)") (class "Default")
      (node (ref "U1") (pin "25") (pinfunction "PA6_25") (pintype "passive+no_connect"))
    )
    (net (code "71") (name "unconnected-(U1-PB4-Pad59)") (class "Default")
      (node (ref "U1") (pin "59") (pinfunction "PB4_59") (pintype "passive+no_connect"))
    )
    (net (code "72") (name "unconnected-(U1-PB12-Pad36)") (class "Default")
      (node (ref "U1") (pin "36") (pinfunction "PB12_36") (pintype "passive+no_connect"))
    )
    (net (code "73") (name "unconnected-(U1-PB14-Pad38)") (class "Default")
      (node (ref "U1") (pin "38") (pinfunction "PB14_38") (pintype "passive+no_connect"))
    )
    (net (code "74") (name "unconnected-(U1-PB15-Pad39)") (class "Default")
      (node (ref "U1") (pin "39") (pinfunction "PB15_39") (pintype "passive+no_connect"))
    )
    (net (code "75") (name "unconnected-(U1-PC0-Pad13)") (class "Default")
      (node (ref "U1") (pin "13") (pinfunction "PC0_13") (pintype "passive+no_connect"))
    )
    (net (code "76") (name "unconnected-(U1-PC5-Pad28)") (class "Default")
      (node (ref "U1") (pin "28") (pinfunction "PC5_28") (pintype "passive+no_connect"))
    )
    (net (code "77") (name "unconnected-(U1-PC6-Pad40)") (class "Default")
      (node (ref "U1") (pin "40") (pinfunction "PC6_40") (pintype "passive+no_connect"))
    )
    (net (code "78") (name "unconnected-(U4-CHRG-Pad1)") (class "Default")
      (node (ref "U4") (pin "1") (pinfunction "CHRG_1") (pintype "passive+no_connect"))
    )
  )
)
